# untitled.net
KiCad netlist of a schematic drawn in EAGLE
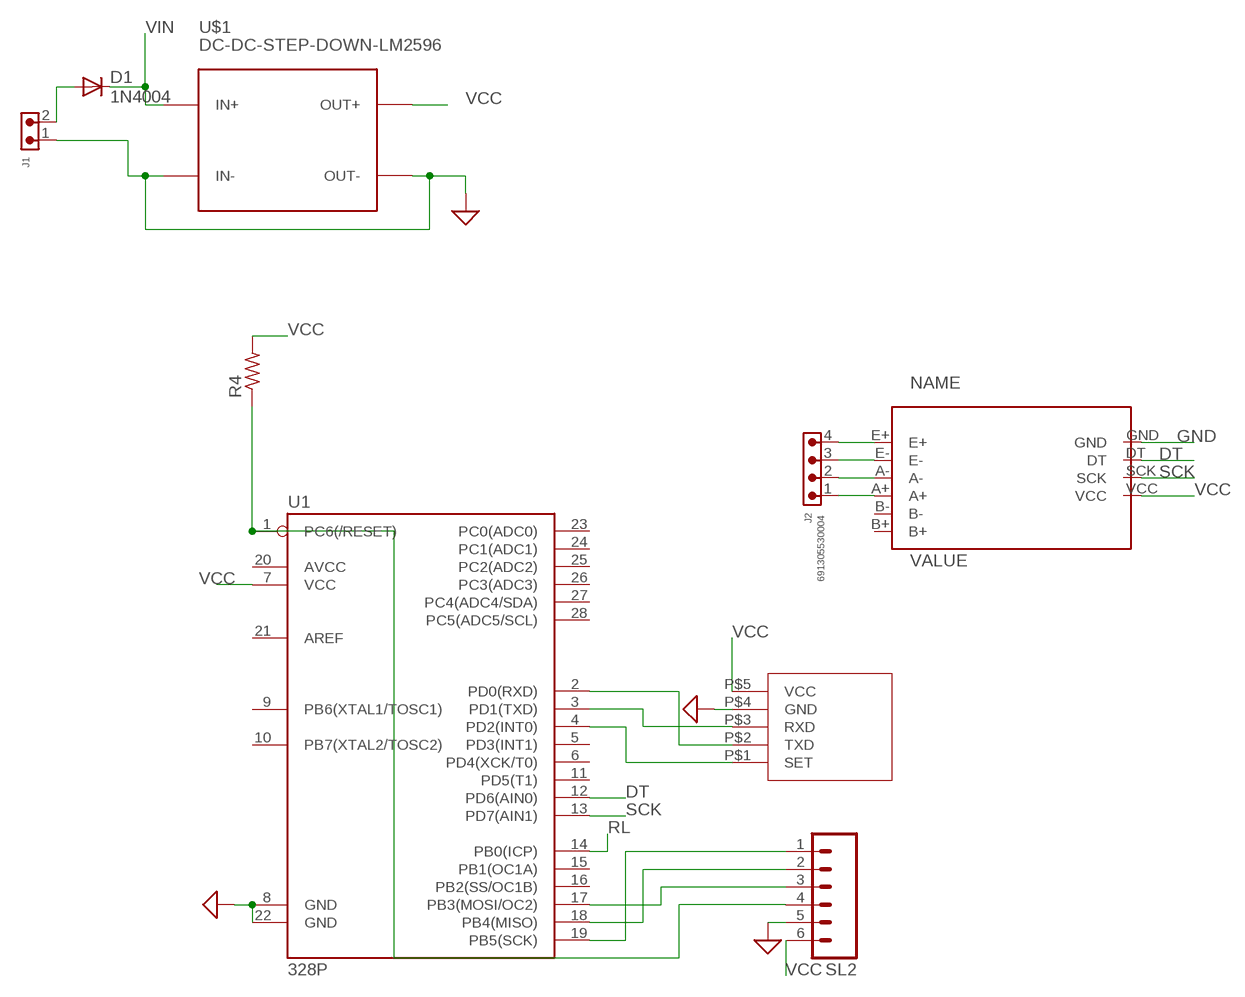
[diagram p0: schematic, sheet 1]

(export (version "E")
  (design (tool "Eeschema 10.0.6"))
  (components
    (comp (ref "D1")
      (value "1N4004")
      (footprint "eagle-import:DO41-10")
      (libsource (lib "eagle-import") (part "1N4004"))
    )
    (comp (ref "J1")
      (value "691305530002")
      (footprint "eagle-import:691305530002")
      (libsource (lib "eagle-import") (part "691305530002"))
    )
    (comp (ref "J2")
      (value "691305530004")
      (footprint "eagle-import:691305530004")
      (libsource (lib "eagle-import") (part "691305530004"))
    )
    (comp (ref "R4")
      (value "R-US_0207/7")
      (footprint "eagle-import:0207_7")
      (libsource (lib "eagle-import") (part "R-US_0207/7"))
    )
    (comp (ref "SL2")
      (value "M06")
      (footprint "eagle-import:06P")
      (libsource (lib "eagle-import") (part "M06"))
    )
    (comp (ref "U$1")
      (value "DC-DC-STEP-DOWN-LM2596")
      (footprint "eagle-import:DC-DC-STEP-DOWN-LM2596")
      (libsource (lib "eagle-import") (part "DC-DC-STEP-DOWN-LM2596"))
    )
    (comp (ref "U$2")
      (value "HX711A")
      (footprint "eagle-import:HX711")
      (libsource (lib "eagle-import") (part "HX711A"))
    )
    (comp (ref "U$3")
      (value "HC12")
      (footprint "eagle-import:HC12")
      (libsource (lib "eagle-import") (part "HC12"))
    )
    (comp (ref "U1")
      (value "328P")
      (footprint "eagle-import:DIP28")
      (libsource (lib "eagle-import") (part "ATMEGA328P_PDIP"))
    )
  )
  (nets
    (net (code "1") (name "/DT") (class "Default")
      (node (ref "U$2") (pin "DT") (pinfunction "DT_DT") (pintype "bidirectional"))
      (node (ref "U1") (pin "12") (pinfunction "PD6(AIN0)_12") (pintype "bidirectional"))
    )
    (net (code "2") (name "/RL") (class "Default")
      (node (ref "U1") (pin "14") (pinfunction "PB0(ICP)_14") (pintype "bidirectional"))
    )
    (net (code "3") (name "/SCK") (class "Default")
      (node (ref "U$2") (pin "SCK") (pinfunction "SCK_SCK") (pintype "bidirectional"))
      (node (ref "U1") (pin "13") (pinfunction "PD7(AIN1)_13") (pintype "bidirectional"))
    )
    (net (code "4") (name "/VCC") (class "Default")
      (node (ref "R4") (pin "2") (pinfunction "2_2") (pintype "passive"))
      (node (ref "SL2") (pin "6") (pinfunction "6_6") (pintype "passive"))
      (node (ref "U$1") (pin "OUT+") (pinfunction "OUT+_OUT+") (pintype "bidirectional"))
      (node (ref "U$2") (pin "VCC") (pinfunction "VCC_VCC") (pintype "bidirectional"))
      (node (ref "U$3") (pin "P$5") (pinfunction "VCC_P$5") (pintype "bidirectional"))
      (node (ref "U1") (pin "7") (pinfunction "VCC_7") (pintype "bidirectional"))
    )
    (net (code "5") (name "/VIN") (class "Default")
      (node (ref "D1") (pin "C") (pinfunction "C_C") (pintype "passive"))
      (node (ref "U$1") (pin "IN+") (pinfunction "IN+_IN+") (pintype "bidirectional"))
    )
    (net (code "6") (name "Net-(D1-PadA)") (class "Default")
      (node (ref "D1") (pin "A") (pinfunction "A_A") (pintype "passive"))
      (node (ref "J1") (pin "2") (pinfunction "2_2") (pintype "passive"))
    )
    (net (code "7") (name "Net-(J2-Pad1)") (class "Default")
      (node (ref "J2") (pin "1") (pinfunction "1_1") (pintype "passive"))
      (node (ref "U$2") (pin "A+") (pinfunction "A+_A+") (pintype "bidirectional"))
    )
    (net (code "8") (name "Net-(J2-Pad2)") (class "Default")
      (node (ref "J2") (pin "2") (pinfunction "2_2") (pintype "passive"))
      (node (ref "U$2") (pin "A-") (pinfunction "A-_A-") (pintype "bidirectional"))
    )
    (net (code "9") (name "Net-(J2-Pad3)") (class "Default")
      (node (ref "J2") (pin "3") (pinfunction "3_3") (pintype "passive"))
      (node (ref "U$2") (pin "E-") (pinfunction "E-_E-") (pintype "bidirectional"))
    )
    (net (code "10") (name "Net-(J2-Pad4)") (class "Default")
      (node (ref "J2") (pin "4") (pinfunction "4_4") (pintype "passive"))
      (node (ref "U$2") (pin "E+") (pinfunction "E+_E+") (pintype "bidirectional"))
    )
    (net (code "11") (name "Net-(U$3-RXD)") (class "Default")
      (node (ref "U$3") (pin "P$3") (pinfunction "RXD_P$3") (pintype "bidirectional"))
      (node (ref "U1") (pin "3") (pinfunction "PD1(TXD)_3") (pintype "bidirectional"))
    )
    (net (code "12") (name "Net-(U$3-SET)") (class "Default")
      (node (ref "U$3") (pin "P$1") (pinfunction "SET_P$1") (pintype "bidirectional"))
      (node (ref "U1") (pin "4") (pinfunction "PD2(INT0)_4") (pintype "bidirectional"))
    )
    (net (code "13") (name "Net-(U$3-TXD)") (class "Default")
      (node (ref "U$3") (pin "P$2") (pinfunction "TXD_P$2") (pintype "bidirectional"))
      (node (ref "U1") (pin "2") (pinfunction "PD0(RXD)_2") (pintype "bidirectional"))
    )
    (net (code "14") (name "Net-(U1-PB3(MOSI{slash}OC2))") (class "Default")
      (node (ref "SL2") (pin "3") (pinfunction "3_3") (pintype "passive"))
      (node (ref "U1") (pin "17") (pinfunction "PB3(MOSI/OC2)_17") (pintype "bidirectional"))
    )
    (net (code "15") (name "Net-(U1-PB4(MISO))") (class "Default")
      (node (ref "SL2") (pin "2") (pinfunction "2_2") (pintype "passive"))
      (node (ref "U1") (pin "18") (pinfunction "PB4(MISO)_18") (pintype "bidirectional"))
    )
    (net (code "16") (name "Net-(U1-PB5(SCK))") (class "Default")
      (node (ref "SL2") (pin "1") (pinfunction "1_1") (pintype "passive"))
      (node (ref "U1") (pin "19") (pinfunction "PB5(SCK)_19") (pintype "bidirectional"))
    )
    (net (code "17") (name "Net-(U1-PC6({slash}RESET))") (class "Default")
      (node (ref "R4") (pin "1") (pinfunction "1_1") (pintype "passive"))
      (node (ref "SL2") (pin "4") (pinfunction "4_4") (pintype "passive"))
      (node (ref "U1") (pin "1") (pinfunction "PC6(/RESET)_1") (pintype "bidirectional"))
    )
    (net (code "18") (name "SUP") (class "Default")
      (node (ref "J1") (pin "1") (pinfunction "1_1") (pintype "passive"))
      (node (ref "SL2") (pin "5") (pinfunction "5_5") (pintype "passive"))
      (node (ref "U$1") (pin "IN-") (pinfunction "IN-_IN-") (pintype "bidirectional"))
      (node (ref "U$1") (pin "OUT-") (pinfunction "OUT-_OUT-") (pintype "bidirectional"))
      (node (ref "U$2") (pin "GND") (pinfunction "GND_GND") (pintype "bidirectional"))
      (node (ref "U$3") (pin "P$4") (pinfunction "GND_P$4") (pintype "bidirectional"))
      (node (ref "U1") (pin "22") (pinfunction "GND_22") (pintype "bidirectional"))
      (node (ref "U1") (pin "8") (pinfunction "GND_8") (pintype "bidirectional"))
    )
    (net (code "19") (name "unconnected-(U$2-PadB+)") (class "Default")
      (node (ref "U$2") (pin "B+") (pinfunction "B+_B+") (pintype "bidirectional"))
    )
    (net (code "20") (name "unconnected-(U$2-PadB-)") (class "Default")
      (node (ref "U$2") (pin "B-") (pinfunction "B-_B-") (pintype "bidirectional"))
    )
    (net (code "21") (name "unconnected-(U1-AREF-Pad21)") (class "Default")
      (node (ref "U1") (pin "21") (pinfunction "AREF_21") (pintype "bidirectional"))
    )
    (net (code "22") (name "unconnected-(U1-AVCC-Pad20)") (class "Default")
      (node (ref "U1") (pin "20") (pinfunction "AVCC_20") (pintype "bidirectional"))
    )
    (net (code "23") (name "unconnected-(U1-PB1(OC1A)-Pad15)") (class "Default")
      (node (ref "U1") (pin "15") (pinfunction "PB1(OC1A)_15") (pintype "bidirectional"))
    )
    (net (code "24") (name "unconnected-(U1-PB2(SS{slash}OC1B)-Pad16)") (class "Default")
      (node (ref "U1") (pin "16") (pinfunction "PB2(SS/OC1B)_16") (pintype "bidirectional"))
    )
    (net (code "25") (name "unconnected-(U1-PB6(XTAL1{slash}TOSC1)-Pad9)") (class "Default")
      (node (ref "U1") (pin "9") (pinfunction "PB6(XTAL1/TOSC1)_9") (pintype "bidirectional"))
    )
    (net (code "26") (name "unconnected-(U1-PB7(XTAL2{slash}TOSC2)-Pad10)") (class "Default")
      (node (ref "U1") (pin "10") (pinfunction "PB7(XTAL2/TOSC2)_10") (pintype "bidirectional"))
    )
    (net (code "27") (name "unconnected-(U1-PC0(ADC0)-Pad23)") (class "Default")
      (node (ref "U1") (pin "23") (pinfunction "PC0(ADC0)_23") (pintype "bidirectional"))
    )
    (net (code "28") (name "unconnected-(U1-PC1(ADC1)-Pad24)") (class "Default")
      (node (ref "U1") (pin "24") (pinfunction "PC1(ADC1)_24") (pintype "bidirectional"))
    )
    (net (code "29") (name "unconnected-(U1-PC2(ADC2)-Pad25)") (class "Default")
      (node (ref "U1") (pin "25") (pinfunction "PC2(ADC2)_25") (pintype "bidirectional"))
    )
    (net (code "30") (name "unconnected-(U1-PC3(ADC3)-Pad26)") (class "Default")
      (node (ref "U1") (pin "26") (pinfunction "PC3(ADC3)_26") (pintype "bidirectional"))
    )
    (net (code "31") (name "unconnected-(U1-PC4(ADC4{slash}SDA)-Pad27)") (class "Default")
      (node (ref "U1") (pin "27") (pinfunction "PC4(ADC4/SDA)_27") (pintype "bidirectional"))
    )
    (net (code "32") (name "unconnected-(U1-PC5(ADC5{slash}SCL)-Pad28)") (class "Default")
      (node (ref "U1") (pin "28") (pinfunction "PC5(ADC5/SCL)_28") (pintype "bidirectional"))
    )
    (net (code "33") (name "unconnected-(U1-PD3(INT1)-Pad5)") (class "Default")
      (node (ref "U1") (pin "5") (pinfunction "PD3(INT1)_5") (pintype "bidirectional"))
    )
    (net (code "34") (name "unconnected-(U1-PD4(XCK{slash}T0)-Pad6)") (class "Default")
      (node (ref "U1") (pin "6") (pinfunction "PD4(XCK/T0)_6") (pintype "bidirectional"))
    )
    (net (code "35") (name "unconnected-(U1-PD5(T1)-Pad11)") (class "Default")
      (node (ref "U1") (pin "11") (pinfunction "PD5(T1)_11") (pintype "bidirectional"))
    )
  )
)
